# main.net
KiCad netlist of a schematic drawn in EAGLE
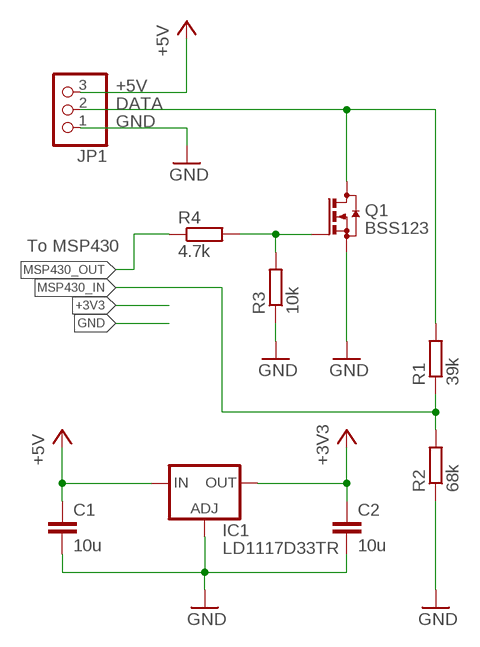
[diagram p0: schematic, sheet 1]

(export (version "E")
  (design (tool "Eeschema 10.0.6"))
  (components
    (comp (ref "C1")
      (value "10u")
      (footprint "eagle-import:C0805")
      (libsource (lib "eagle-import") (part "C-EUC0805"))
    )
    (comp (ref "C2")
      (value "10u")
      (footprint "eagle-import:C0805")
      (libsource (lib "eagle-import") (part "C-EUC0805"))
    )
    (comp (ref "IC1")
      (value "LD1117D33TR")
      (footprint "eagle-import:SOT223")
      (libsource (lib "eagle-import") (part "LD117A?STR"))
    )
    (comp (ref "JP1")
      (value "PINHD-1X3")
      (footprint "eagle-import:1X03")
      (libsource (lib "eagle-import") (part "PINHD-1X3"))
    )
    (comp (ref "Q1")
      (value "BSS123")
      (footprint "eagle-import:SOT23")
      (libsource (lib "eagle-import") (part "BSS123"))
    )
    (comp (ref "R1")
      (value "39k")
      (footprint "eagle-import:M0805")
      (libsource (lib "eagle-import") (part "R-EU_M0805"))
    )
    (comp (ref "R2")
      (value "68k")
      (footprint "eagle-import:M0805")
      (libsource (lib "eagle-import") (part "R-EU_M0805"))
    )
    (comp (ref "R3")
      (value "10k")
      (footprint "eagle-import:M0805")
      (libsource (lib "eagle-import") (part "R-EU_M0805"))
    )
    (comp (ref "R4")
      (value "4.7k")
      (footprint "eagle-import:M0805")
      (libsource (lib "eagle-import") (part "R-EU_M0805"))
    )
  )
  (nets
    (net (code "1") (name "+3V3") (class "Default")
      (node (ref "C2") (pin "1") (pinfunction "1_1") (pintype "passive"))
      (node (ref "IC1") (pin "4") (pinfunction "OUT_4") (pintype "passive"))
    )
    (net (code "2") (name "+5V") (class "Default")
      (node (ref "C1") (pin "1") (pinfunction "1_1") (pintype "passive"))
      (node (ref "IC1") (pin "3") (pinfunction "IN_3") (pintype "input"))
      (node (ref "JP1") (pin "3") (pinfunction "3_3") (pintype "passive"))
    )
    (net (code "3") (name "/DATA") (class "Default")
      (node (ref "JP1") (pin "2") (pinfunction "2_2") (pintype "passive"))
      (node (ref "Q1") (pin "3") (pinfunction "D_3") (pintype "passive"))
      (node (ref "R1") (pin "2") (pinfunction "2_2") (pintype "passive"))
    )
    (net (code "4") (name "GND") (class "Default")
      (node (ref "C1") (pin "2") (pinfunction "2_2") (pintype "passive"))
      (node (ref "C2") (pin "2") (pinfunction "2_2") (pintype "passive"))
      (node (ref "IC1") (pin "1") (pinfunction "ADJ_1") (pintype "input"))
      (node (ref "JP1") (pin "1") (pinfunction "1_1") (pintype "passive"))
      (node (ref "Q1") (pin "2") (pinfunction "S_2") (pintype "passive"))
      (node (ref "R2") (pin "1") (pinfunction "1_1") (pintype "passive"))
      (node (ref "R3") (pin "1") (pinfunction "1_1") (pintype "passive"))
    )
    (net (code "5") (name "MSP430_IN") (class "Default")
      (node (ref "R1") (pin "1") (pinfunction "1_1") (pintype "passive"))
      (node (ref "R2") (pin "2") (pinfunction "2_2") (pintype "passive"))
    )
    (net (code "6") (name "MSP430_OUT") (class "Default")
      (node (ref "R4") (pin "1") (pinfunction "1_1") (pintype "passive"))
    )
    (net (code "7") (name "Net-(Q1-G)") (class "Default")
      (node (ref "Q1") (pin "1") (pinfunction "G_1") (pintype "passive"))
      (node (ref "R3") (pin "2") (pinfunction "2_2") (pintype "passive"))
      (node (ref "R4") (pin "2") (pinfunction "2_2") (pintype "passive"))
    )
  )
)
